# I2S_Audio.net
KiCad netlist of a schematic drawn in Altium Designer
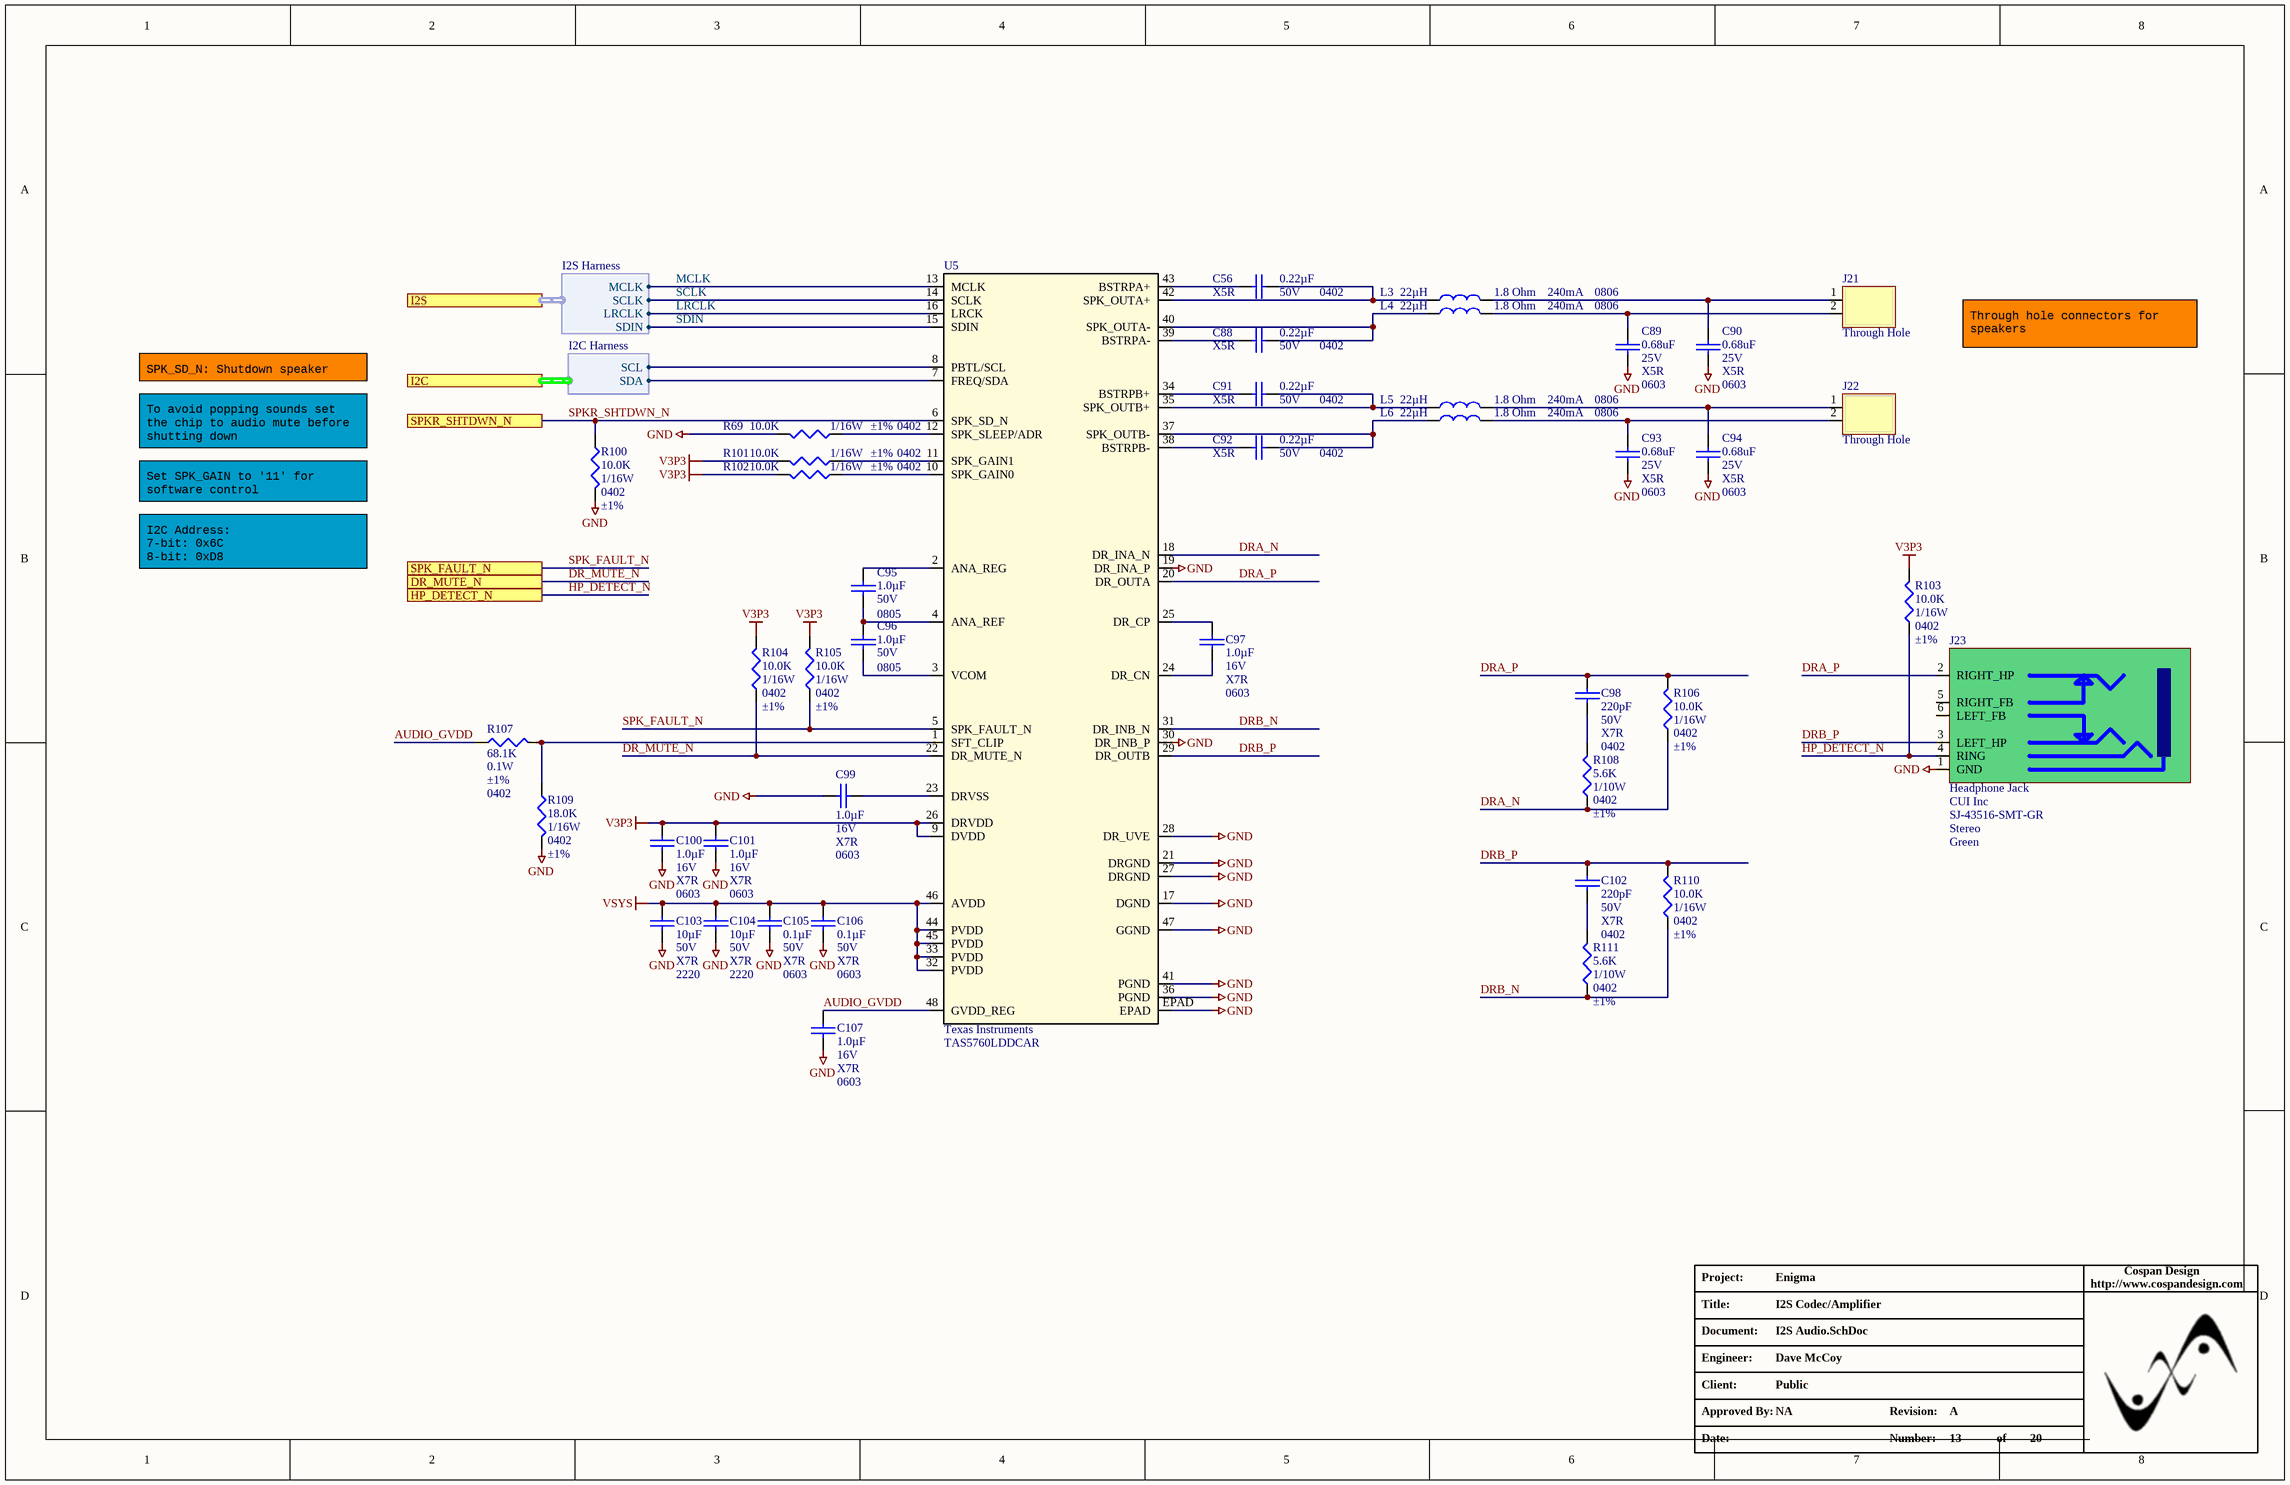
[diagram p0: I2S Audio.SchDoc]

(export (version "E")
  (design (tool "Eeschema 10.0.6"))
  (components
    (comp (ref "C56")
      (value "C_0402_0.22UF_50V")
      (footprint "C_0402")
      (description "CAP CER 0.22UF 50V X5R 0402")
      (fields
        (field (name "MANUFACTURER") "Taiyo Yuden")
        (field (name "MANUFACTURER PART NUMBER") "UMK105BJ224KV-F")
        (field (name "CAPACITANCE") "0.22µF")
        (field (name "VOLTAGE - RATED") "50V")
        (field (name "TEMPERATURE COEFFICIENT") "X5R")
        (field (name "PACKAGE / CASE") "0402")
      )
      (libsource (lib "Main Library") (part "C_0402_0.22UF_50V"))
    )
    (comp (ref "C88")
      (value "C_0402_0.22UF_50V")
      (footprint "C_0402")
      (description "CAP CER 0.22UF 50V X5R 0402")
      (fields
        (field (name "MANUFACTURER") "Taiyo Yuden")
        (field (name "MANUFACTURER PART NUMBER") "UMK105BJ224KV-F")
        (field (name "CAPACITANCE") "0.22µF")
        (field (name "VOLTAGE - RATED") "50V")
        (field (name "TEMPERATURE COEFFICIENT") "X5R")
        (field (name "PACKAGE / CASE") "0402")
      )
      (libsource (lib "Main Library") (part "C_0402_0.22UF_50V"))
    )
    (comp (ref "C89")
      (value "C_0603_0.68uF_25V")
      (footprint "C_ERA-0603")
      (description "CAP CER 0.68UF 25V X5R 0603")
      (fields
        (field (name "MANUFACTURER") "Wurth Electronics Inc.")
        (field (name "MANUFACTURER PART NUMBER") "885012106021")
        (field (name "CAPACITANCE") "0.68uF")
        (field (name "VOLTAGE - RATED") "25V")
        (field (name "TEMPERATURE COEFFICIENT") "X5R")
        (field (name "PACKAGE / CASE") "0603")
      )
      (libsource (lib "Cospan Design") (part "C_0603_0.68uF_25V"))
    )
    (comp (ref "C90")
      (value "C_0603_0.68uF_25V")
      (footprint "C_ERA-0603")
      (description "CAP CER 0.68UF 25V X5R 0603")
      (fields
        (field (name "MANUFACTURER") "Wurth Electronics Inc.")
        (field (name "MANUFACTURER PART NUMBER") "885012106021")
        (field (name "CAPACITANCE") "0.68uF")
        (field (name "VOLTAGE - RATED") "25V")
        (field (name "TEMPERATURE COEFFICIENT") "X5R")
        (field (name "PACKAGE / CASE") "0603")
      )
      (libsource (lib "Cospan Design") (part "C_0603_0.68uF_25V"))
    )
    (comp (ref "C91")
      (value "C_0402_0.22UF_50V")
      (footprint "C_0402")
      (description "CAP CER 0.22UF 50V X5R 0402")
      (fields
        (field (name "MANUFACTURER") "Taiyo Yuden")
        (field (name "MANUFACTURER PART NUMBER") "UMK105BJ224KV-F")
        (field (name "CAPACITANCE") "0.22µF")
        (field (name "VOLTAGE - RATED") "50V")
        (field (name "TEMPERATURE COEFFICIENT") "X5R")
        (field (name "PACKAGE / CASE") "0402")
      )
      (libsource (lib "Main Library") (part "C_0402_0.22UF_50V"))
    )
    (comp (ref "C92")
      (value "C_0402_0.22UF_50V")
      (footprint "C_0402")
      (description "CAP CER 0.22UF 50V X5R 0402")
      (fields
        (field (name "MANUFACTURER") "Taiyo Yuden")
        (field (name "MANUFACTURER PART NUMBER") "UMK105BJ224KV-F")
        (field (name "CAPACITANCE") "0.22µF")
        (field (name "VOLTAGE - RATED") "50V")
        (field (name "TEMPERATURE COEFFICIENT") "X5R")
        (field (name "PACKAGE / CASE") "0402")
      )
      (libsource (lib "Main Library") (part "C_0402_0.22UF_50V"))
    )
    (comp (ref "C93")
      (value "C_0603_0.68uF_25V")
      (footprint "C_ERA-0603")
      (description "CAP CER 0.68UF 25V X5R 0603")
      (fields
        (field (name "MANUFACTURER") "Wurth Electronics Inc.")
        (field (name "MANUFACTURER PART NUMBER") "885012106021")
        (field (name "CAPACITANCE") "0.68uF")
        (field (name "VOLTAGE - RATED") "25V")
        (field (name "TEMPERATURE COEFFICIENT") "X5R")
        (field (name "PACKAGE / CASE") "0603")
      )
      (libsource (lib "Cospan Design") (part "C_0603_0.68uF_25V"))
    )
    (comp (ref "C94")
      (value "C_0603_0.68uF_25V")
      (footprint "C_ERA-0603")
      (description "CAP CER 0.68UF 25V X5R 0603")
      (fields
        (field (name "MANUFACTURER") "Wurth Electronics Inc.")
        (field (name "MANUFACTURER PART NUMBER") "885012106021")
        (field (name "CAPACITANCE") "0.68uF")
        (field (name "VOLTAGE - RATED") "25V")
        (field (name "TEMPERATURE COEFFICIENT") "X5R")
        (field (name "PACKAGE / CASE") "0603")
      )
      (libsource (lib "Cospan Design") (part "C_0603_0.68uF_25V"))
    )
    (comp (ref "C95")
      (value "1.0uF")
      (footprint "C_ERA-0805")
      (description "CAP CER 1UF 50V X7R 0805")
      (fields
        (field (name "MANUFACTURER") "Murata Electronics North America")
        (field (name "MANUFACTURER PART NUMBER") "GRM21BR71H105KA12L")
        (field (name "CAPACITANCE") "1.0µF")
        (field (name "VOLTAGE - RATED") "50V")
        (field (name "PACKAGE / CASE") "0805")
      )
      (libsource (lib "Main Library") (part "C_0805_1.0uF_50V"))
    )
    (comp (ref "C96")
      (value "1.0uF")
      (footprint "C_ERA-0805")
      (description "CAP CER 1UF 50V X7R 0805")
      (fields
        (field (name "MANUFACTURER") "Murata Electronics North America")
        (field (name "MANUFACTURER PART NUMBER") "GRM21BR71H105KA12L")
        (field (name "CAPACITANCE") "1.0µF")
        (field (name "VOLTAGE - RATED") "50V")
        (field (name "PACKAGE / CASE") "0805")
      )
      (libsource (lib "Main Library") (part "C_0805_1.0uF_50V"))
    )
    (comp (ref "C97")
      (value "1.0uF")
      (footprint "C_ERA-0603")
      (description "CAP CER 1UF 16V 10% X7R 0603")
      (fields
        (field (name "MANUFACTURER") "Yageo")
        (field (name "MANUFACTURER PART NUMBER") "CC0603KRX7R7BB105")
        (field (name "CAPACITANCE") "1.0µF")
        (field (name "VOLTAGE - RATED") "16V")
        (field (name "TEMPERATURE COEFFICIENT") "X7R")
        (field (name "PACKAGE / CASE") "0603")
      )
      (libsource (lib "Main LibraryX") (part "C_0603_1.0uF_16V"))
    )
    (comp (ref "C98")
      (value "220pF")
      (footprint "C_0402")
      (description "CAP CER 220PF 50V 10% X7R 0402")
      (fields
        (field (name "MANUFACTURER") "Murata Electronics North America")
        (field (name "MANUFACTURER PART NUMBER") "GRM155R71H221KA01D")
        (field (name "CAPACITANCE") "220pF")
        (field (name "VOLTAGE - RATED") "50V")
        (field (name "TEMPERATURE COEFFICIENT") "X7R")
        (field (name "PACKAGE / CASE") "0402")
      )
      (libsource (lib "Main Library") (part "C_0402_220PF_50V"))
    )
    (comp (ref "C99")
      (value "1.0uF")
      (footprint "C_ERA-0603")
      (description "CAP CER 1UF 16V 10% X7R 0603")
      (fields
        (field (name "MANUFACTURER") "Yageo")
        (field (name "MANUFACTURER PART NUMBER") "CC0603KRX7R7BB105")
        (field (name "CAPACITANCE") "1.0µF")
        (field (name "VOLTAGE - RATED") "16V")
        (field (name "TEMPERATURE COEFFICIENT") "X7R")
        (field (name "PACKAGE / CASE") "0603")
      )
      (libsource (lib "Main LibraryX") (part "C_0603_1.0uF_16V"))
    )
    (comp (ref "C100")
      (value "1.0uF")
      (footprint "C_ERA-0603")
      (description "CAP CER 1UF 16V 10% X7R 0603")
      (fields
        (field (name "MANUFACTURER") "Yageo")
        (field (name "MANUFACTURER PART NUMBER") "CC0603KRX7R7BB105")
        (field (name "CAPACITANCE") "1.0µF")
        (field (name "VOLTAGE - RATED") "16V")
        (field (name "TEMPERATURE COEFFICIENT") "X7R")
        (field (name "PACKAGE / CASE") "0603")
      )
      (libsource (lib "Main LibraryX") (part "C_0603_1.0uF_16V"))
    )
    (comp (ref "C101")
      (value "1.0uF")
      (footprint "C_ERA-0603")
      (description "CAP CER 1UF 16V 10% X7R 0603")
      (fields
        (field (name "MANUFACTURER") "Yageo")
        (field (name "MANUFACTURER PART NUMBER") "CC0603KRX7R7BB105")
        (field (name "CAPACITANCE") "1.0µF")
        (field (name "VOLTAGE - RATED") "16V")
        (field (name "TEMPERATURE COEFFICIENT") "X7R")
        (field (name "PACKAGE / CASE") "0603")
      )
      (libsource (lib "Main LibraryX") (part "C_0603_1.0uF_16V"))
    )
    (comp (ref "C102")
      (value "220pF")
      (footprint "C_0402")
      (description "CAP CER 220PF 50V 10% X7R 0402")
      (fields
        (field (name "MANUFACTURER") "Murata Electronics North America")
        (field (name "MANUFACTURER PART NUMBER") "GRM155R71H221KA01D")
        (field (name "CAPACITANCE") "220pF")
        (field (name "VOLTAGE - RATED") "50V")
        (field (name "TEMPERATURE COEFFICIENT") "X7R")
        (field (name "PACKAGE / CASE") "0402")
      )
      (libsource (lib "Main Library") (part "C_0402_220PF_50V"))
    )
    (comp (ref "C103")
      (value "10µF")
      (footprint "C_ERA-2220")
      (description "CAP CER 10UF 50V X7R 20% 2220")
      (fields
        (field (name "MANUFACTURER") "TDK Corporation")
        (field (name "MANUFACTURER PART NUMBER") "C5750X7R1H106K230KB")
        (field (name "CAPACITANCE") "10µF")
        (field (name "VOLTAGE - RATED") "50V")
        (field (name "TEMPERATURE COEFFICIENT") "X7R")
        (field (name "PACKAGE / CASE") "2220")
      )
      (libsource (lib "Main LibraryX") (part "C_2220_10UF_50V"))
    )
    (comp (ref "C104")
      (value "10µF")
      (footprint "C_ERA-2220")
      (description "CAP CER 10UF 50V X7R 20% 2220")
      (fields
        (field (name "MANUFACTURER") "TDK Corporation")
        (field (name "MANUFACTURER PART NUMBER") "C5750X7R1H106K230KB")
        (field (name "CAPACITANCE") "10µF")
        (field (name "VOLTAGE - RATED") "50V")
        (field (name "TEMPERATURE COEFFICIENT") "X7R")
        (field (name "PACKAGE / CASE") "2220")
      )
      (libsource (lib "Main LibraryX") (part "C_2220_10UF_50V"))
    )
    (comp (ref "C105")
      (value "C_0603_0.1µF")
      (footprint "C_ERA-0603")
      (description "CAP CER 0.1UF 50V X7R 0603")
      (fields
        (field (name "MANUFACTURER") "Samsung Electro-Mechanics America, Inc.")
        (field (name "MANUFACTURER PART NUMBER") "CL10B104KB8SFNC")
        (field (name "CAPACITANCE") "0.1µF")
        (field (name "VOLTAGE - RATED") "50V")
        (field (name "TEMPERATURE COEFFICIENT") "X7R")
        (field (name "PACKAGE / CASE") "0603")
      )
      (libsource (lib "Cospan Design") (part "C_0603_0.1µF"))
    )
    (comp (ref "C106")
      (value "C_0603_0.1µF")
      (footprint "C_ERA-0603")
      (description "CAP CER 0.1UF 50V X7R 0603")
      (fields
        (field (name "MANUFACTURER") "Samsung Electro-Mechanics America, Inc.")
        (field (name "MANUFACTURER PART NUMBER") "CL10B104KB8SFNC")
        (field (name "CAPACITANCE") "0.1µF")
        (field (name "VOLTAGE - RATED") "50V")
        (field (name "TEMPERATURE COEFFICIENT") "X7R")
        (field (name "PACKAGE / CASE") "0603")
      )
      (libsource (lib "Cospan Design") (part "C_0603_0.1µF"))
    )
    (comp (ref "C107")
      (value "1.0uF")
      (footprint "C_ERA-0603")
      (description "CAP CER 1UF 16V 10% X7R 0603")
      (fields
        (field (name "MANUFACTURER") "Yageo")
        (field (name "MANUFACTURER PART NUMBER") "CC0603KRX7R7BB105")
        (field (name "CAPACITANCE") "1.0µF")
        (field (name "VOLTAGE - RATED") "16V")
        (field (name "TEMPERATURE COEFFICIENT") "X7R")
        (field (name "PACKAGE / CASE") "0603")
      )
      (libsource (lib "Main LibraryX") (part "C_0603_1.0uF_16V"))
    )
    (comp (ref "J21")
      (value "J_HDR1X2_JUMPER")
      (footprint "HDR_1X2")
      (description "CONN HEADER .100\" 2POS TIN PCB")
      (fields
        (field (name "MANUFACTURER") "Samtec")
        (field (name "MANUFACTURER PART NUMBER") "TSW-102-07-T-S")
        (field (name "MOUNTING TYPE") "Through Hole")
      )
      (libsource (lib "Main Library") (part "J_HDR1X2_JUMPER"))
    )
    (comp (ref "J22")
      (value "J_HDR1X2_JUMPER")
      (footprint "HDR_1X2")
      (description "CONN HEADER .100\" 2POS TIN PCB")
      (fields
        (field (name "MANUFACTURER") "Samtec")
        (field (name "MANUFACTURER PART NUMBER") "TSW-102-07-T-S")
        (field (name "MOUNTING TYPE") "Through Hole")
      )
      (libsource (lib "Main Library") (part "J_HDR1X2_JUMPER"))
    )
    (comp (ref "J23")
      (value "Headphone Jack")
      (footprint "HEADPHONE_JACK")
      (description "CONN AUDIO JACK 3.5MM 4COND SMD")
      (fields
        (field (name "MANUFACTURER") "CUI Inc")
        (field (name "MANUFACTURER PART NUMBER") "SJ-43516-SMT-GR")
        (field (name "SIGNAL LINES") "Stereo")
        (field (name "COLOR") "Green")
      )
      (libsource (lib "Main Library") (part "J_HEADPHONE_JACK"))
    )
    (comp (ref "L3")
      (value "CBC2016T220K")
      (footprint "L_0806")
      (description "INDUCTOR 22UH 10% 0806 SMD")
      (fields
        (field (name "MANUFACTURER") "Taiyo Yuden")
        (field (name "TOLERANCE") "±10%")
        (field (name "CURRENT") "240mA")
        (field (name "PACKAGE / CASE") "0806")
        (field (name "INDUCTANCE") "22µH")
        (field (name "DC RESISTANCE (DCR)") "1.8 Ohm")
      )
      (libsource (lib "Main Library") (part "L_0806_22uH"))
    )
    (comp (ref "L4")
      (value "CBC2016T220K")
      (footprint "L_0806")
      (description "INDUCTOR 22UH 10% 0806 SMD")
      (fields
        (field (name "MANUFACTURER") "Taiyo Yuden")
        (field (name "TOLERANCE") "±10%")
        (field (name "CURRENT") "240mA")
        (field (name "PACKAGE / CASE") "0806")
        (field (name "INDUCTANCE") "22µH")
        (field (name "DC RESISTANCE (DCR)") "1.8 Ohm")
      )
      (libsource (lib "Main Library") (part "L_0806_22uH"))
    )
    (comp (ref "L5")
      (value "CBC2016T220K")
      (footprint "L_0806")
      (description "INDUCTOR 22UH 10% 0806 SMD")
      (fields
        (field (name "MANUFACTURER") "Taiyo Yuden")
        (field (name "TOLERANCE") "±10%")
        (field (name "CURRENT") "240mA")
        (field (name "PACKAGE / CASE") "0806")
        (field (name "INDUCTANCE") "22µH")
        (field (name "DC RESISTANCE (DCR)") "1.8 Ohm")
      )
      (libsource (lib "Main Library") (part "L_0806_22uH"))
    )
    (comp (ref "L6")
      (value "CBC2016T220K")
      (footprint "L_0806")
      (description "INDUCTOR 22UH 10% 0806 SMD")
      (fields
        (field (name "MANUFACTURER") "Taiyo Yuden")
        (field (name "TOLERANCE") "±10%")
        (field (name "CURRENT") "240mA")
        (field (name "PACKAGE / CASE") "0806")
        (field (name "INDUCTANCE") "22µH")
        (field (name "DC RESISTANCE (DCR)") "1.8 Ohm")
      )
      (libsource (lib "Main Library") (part "L_0806_22uH"))
    )
    (comp (ref "R69")
      (value "R_0402_10.0K")
      (footprint "R_0402")
      (description "RES 10.0K OHM 1/16W 1% 0402 SMD")
      (fields
        (field (name "MANUFACTURER") "Stackpole Electronics Inc")
        (field (name "MANUFACTURER PART NUMBER") "RMCF0402FT10K0")
        (field (name "RESISTANCE IN OHMS") "10.0K")
        (field (name "POWER (WATTS)") "1/16W")
        (field (name "CASE") "0402")
        (field (name "TOLERANCE") "±1%")
      )
      (libsource (lib "Main Library") (part "R_0402_10.0K"))
    )
    (comp (ref "R100")
      (value "R_0402_10.0K")
      (footprint "R_0402")
      (description "RES 10.0K OHM 1/16W 1% 0402 SMD")
      (fields
        (field (name "MANUFACTURER") "Stackpole Electronics Inc")
        (field (name "MANUFACTURER PART NUMBER") "RMCF0402FT10K0")
        (field (name "RESISTANCE IN OHMS") "10.0K")
        (field (name "POWER (WATTS)") "1/16W")
        (field (name "CASE") "0402")
        (field (name "TOLERANCE") "±1%")
      )
      (libsource (lib "Main Library") (part "R_0402_10.0K"))
    )
    (comp (ref "R101")
      (value "R_0402_10.0K")
      (footprint "R_0402")
      (description "RES 10.0K OHM 1/16W 1% 0402 SMD")
      (fields
        (field (name "MANUFACTURER") "Stackpole Electronics Inc")
        (field (name "MANUFACTURER PART NUMBER") "RMCF0402FT10K0")
        (field (name "RESISTANCE IN OHMS") "10.0K")
        (field (name "POWER (WATTS)") "1/16W")
        (field (name "CASE") "0402")
        (field (name "TOLERANCE") "±1%")
      )
      (libsource (lib "Main Library") (part "R_0402_10.0K"))
    )
    (comp (ref "R102")
      (value "R_0402_10.0K")
      (footprint "R_0402")
      (description "RES 10.0K OHM 1/16W 1% 0402 SMD")
      (fields
        (field (name "MANUFACTURER") "Stackpole Electronics Inc")
        (field (name "MANUFACTURER PART NUMBER") "RMCF0402FT10K0")
        (field (name "RESISTANCE IN OHMS") "10.0K")
        (field (name "POWER (WATTS)") "1/16W")
        (field (name "CASE") "0402")
        (field (name "TOLERANCE") "±1%")
      )
      (libsource (lib "Main Library") (part "R_0402_10.0K"))
    )
    (comp (ref "R103")
      (value "R_0402_10.0K")
      (footprint "R_0402")
      (description "RES 10.0K OHM 1/16W 1% 0402 SMD")
      (fields
        (field (name "MANUFACTURER") "Stackpole Electronics Inc")
        (field (name "MANUFACTURER PART NUMBER") "RMCF0402FT10K0")
        (field (name "RESISTANCE IN OHMS") "10.0K")
        (field (name "POWER (WATTS)") "1/16W")
        (field (name "CASE") "0402")
        (field (name "TOLERANCE") "±1%")
      )
      (libsource (lib "Main Library") (part "R_0402_10.0K"))
    )
    (comp (ref "R104")
      (value "R_0402_10.0K")
      (footprint "R_0402")
      (description "RES 10.0K OHM 1/16W 1% 0402 SMD")
      (fields
        (field (name "MANUFACTURER") "Stackpole Electronics Inc")
        (field (name "MANUFACTURER PART NUMBER") "RMCF0402FT10K0")
        (field (name "RESISTANCE IN OHMS") "10.0K")
        (field (name "POWER (WATTS)") "1/16W")
        (field (name "CASE") "0402")
        (field (name "TOLERANCE") "±1%")
      )
      (libsource (lib "Main Library") (part "R_0402_10.0K"))
    )
    (comp (ref "R105")
      (value "R_0402_10.0K")
      (footprint "R_0402")
      (description "RES 10.0K OHM 1/16W 1% 0402 SMD")
      (fields
        (field (name "MANUFACTURER") "Stackpole Electronics Inc")
        (field (name "MANUFACTURER PART NUMBER") "RMCF0402FT10K0")
        (field (name "RESISTANCE IN OHMS") "10.0K")
        (field (name "POWER (WATTS)") "1/16W")
        (field (name "CASE") "0402")
        (field (name "TOLERANCE") "±1%")
      )
      (libsource (lib "Main Library") (part "R_0402_10.0K"))
    )
    (comp (ref "R106")
      (value "R_0402_10.0K")
      (footprint "R_0402")
      (description "RES 10.0K OHM 1/16W 1% 0402 SMD")
      (fields
        (field (name "MANUFACTURER") "Stackpole Electronics Inc")
        (field (name "MANUFACTURER PART NUMBER") "RMCF0402FT10K0")
        (field (name "RESISTANCE IN OHMS") "10.0K")
        (field (name "POWER (WATTS)") "1/16W")
        (field (name "CASE") "0402")
        (field (name "TOLERANCE") "±1%")
      )
      (libsource (lib "Main Library") (part "R_0402_10.0K"))
    )
    (comp (ref "R107")
      (value "R_0402_68.1K")
      (footprint "R_0402")
      (description "RES 68.1K OHM 1/10W 1% 0402 SMD")
      (fields
        (field (name "MANUFACTURER") "Panasonic - ECG")
        (field (name "MANUFACTURER PART NUMBER") "ERJ-2RKF6812X")
        (field (name "RESISTANCE IN OHMS") "68.1K")
        (field (name "POWER (WATTS)") "0.1W")
        (field (name "TOLERANCE") "±1%")
        (field (name "CASE") "0402")
      )
      (libsource (lib "Main Library") (part "R_0402_68.1K"))
    )
    (comp (ref "R108")
      (value "5.6k Ohms")
      (footprint "R_0402")
      (description "RES 5.60K OHM 1/10W 1% 0402 SMD")
      (fields
        (field (name "MANUFACTURER") "Yageo")
        (field (name "MANUFACTURER PART NUMBER") "RC0402FR-075K6L")
        (field (name "RESISTANCE IN OHMS") "5.6K")
        (field (name "POWER (WATTS)") "1/10W")
        (field (name "CASE") "0402")
        (field (name "TOLERANCE") "±1%")
      )
      (libsource (lib "Main LibraryX") (part "R_0402_5.6K"))
    )
    (comp (ref "R109")
      (value "18.0k Ohms")
      (footprint "R_0402")
      (description "RES SMD 18K OHM 1% 1/16W 0402")
      (fields
        (field (name "MANUFACTURER") "Yageo")
        (field (name "MANUFACTURER PART NUMBER") "RC0402FR-0718KL")
        (field (name "RESISTANCE IN OHMS") "18.0K")
        (field (name "POWER (WATTS)") "1/16W")
        (field (name "CASE") "0402")
        (field (name "TOLERANCE") "±1%")
      )
      (libsource (lib "Cospan Design") (part "R_0402_18.0K"))
    )
    (comp (ref "R110")
      (value "R_0402_10.0K")
      (footprint "R_0402")
      (description "RES 10.0K OHM 1/16W 1% 0402 SMD")
      (fields
        (field (name "MANUFACTURER") "Stackpole Electronics Inc")
        (field (name "MANUFACTURER PART NUMBER") "RMCF0402FT10K0")
        (field (name "RESISTANCE IN OHMS") "10.0K")
        (field (name "POWER (WATTS)") "1/16W")
        (field (name "CASE") "0402")
        (field (name "TOLERANCE") "±1%")
      )
      (libsource (lib "Main Library") (part "R_0402_10.0K"))
    )
    (comp (ref "R111")
      (value "5.6k Ohms")
      (footprint "R_0402")
      (description "RES 5.60K OHM 1/10W 1% 0402 SMD")
      (fields
        (field (name "MANUFACTURER") "Yageo")
        (field (name "MANUFACTURER PART NUMBER") "RC0402FR-075K6L")
        (field (name "RESISTANCE IN OHMS") "5.6K")
        (field (name "POWER (WATTS)") "1/10W")
        (field (name "CASE") "0402")
        (field (name "TOLERANCE") "±1%")
      )
      (libsource (lib "Main LibraryX") (part "R_0402_5.6K"))
    )
    (comp (ref "U5")
      (value "U_TAS5760LDDCAR")
      (footprint "DCA48_6P4X3P6")
      (description "IC AUDIO AMP DGTL D 48HTSSOP")
      (fields
        (field (name "MANUFACTURER 1") "Texas Instruments")
        (field (name "MANUFACTURER PART NUMBER 1") "TAS5760LDDCAR")
      )
      (libsource (lib "Cospan Design") (part "U_TAS5760LDDCAR"))
    )
  )
  (nets
    (net (code "4") (name "/AUDIO_GVDD") (class "Default")
      (node (ref "C107") (pin "2") (pinfunction "2_2") (pintype "passive"))
      (node (ref "R107") (pin "1") (pinfunction "1_1") (pintype "passive"))
      (node (ref "U5") (pin "48") (pinfunction "GVDD_REG_48") (pintype "passive"))
    )
    (net (code "5") (name "/DRA_N") (class "Default")
      (node (ref "R106") (pin "2") (pinfunction "2_2") (pintype "passive"))
      (node (ref "R108") (pin "2") (pinfunction "2_2") (pintype "passive"))
      (node (ref "U5") (pin "18") (pinfunction "DR_INA_N_18") (pintype "passive"))
    )
    (net (code "6") (name "/DRA_P") (class "Default")
      (node (ref "C98") (pin "2") (pinfunction "2_2") (pintype "passive"))
      (node (ref "J23") (pin "2") (pinfunction "RIGHT_HP_2") (pintype "passive"))
      (node (ref "R106") (pin "1") (pinfunction "1_1") (pintype "passive"))
      (node (ref "U5") (pin "20") (pinfunction "DR_OUTA_20") (pintype "passive"))
    )
    (net (code "7") (name "/DRB_N") (class "Default")
      (node (ref "R110") (pin "2") (pinfunction "2_2") (pintype "passive"))
      (node (ref "R111") (pin "2") (pinfunction "2_2") (pintype "passive"))
      (node (ref "U5") (pin "31") (pinfunction "DR_INB_N_31") (pintype "passive"))
    )
    (net (code "8") (name "/DRB_P") (class "Default")
      (node (ref "C102") (pin "2") (pinfunction "2_2") (pintype "passive"))
      (node (ref "J23") (pin "3") (pinfunction "LEFT_HP_3") (pintype "passive"))
      (node (ref "R110") (pin "1") (pinfunction "1_1") (pintype "passive"))
      (node (ref "U5") (pin "29") (pinfunction "DR_OUTB_29") (pintype "passive"))
    )
    (net (code "9") (name "/DR_MUTE_N") (class "Default")
      (node (ref "R104") (pin "1") (pinfunction "1_1") (pintype "passive"))
      (node (ref "U5") (pin "22") (pinfunction "DR_MUTE_N_22") (pintype "passive"))
    )
    (net (code "10") (name "/HP_DETECT_N") (class "Default")
      (node (ref "J23") (pin "4") (pinfunction "RING_4") (pintype "passive"))
      (node (ref "R103") (pin "2") (pinfunction "2_2") (pintype "passive"))
    )
    (net (code "11") (name "/LRCLK") (class "Default")
      (node (ref "U5") (pin "16") (pinfunction "LRCK_16") (pintype "passive"))
    )
    (net (code "12") (name "/MCLK") (class "Default")
      (node (ref "U5") (pin "13") (pinfunction "MCLK_13") (pintype "passive"))
    )
    (net (code "13") (name "/SCL") (class "Default")
      (node (ref "U5") (pin "8") (pinfunction "PBTL/SCL_8") (pintype "passive"))
    )
    (net (code "14") (name "/SCLK") (class "Default")
      (node (ref "U5") (pin "14") (pinfunction "SCLK_14") (pintype "passive"))
    )
    (net (code "15") (name "/SDA") (class "Default")
      (node (ref "U5") (pin "7") (pinfunction "FREQ/SDA_7") (pintype "passive"))
    )
    (net (code "16") (name "/SDIN") (class "Default")
      (node (ref "U5") (pin "15") (pinfunction "SDIN_15") (pintype "passive"))
    )
    (net (code "17") (name "/SPKR_SHTDWN_N") (class "Default")
      (node (ref "R100") (pin "2") (pinfunction "2_2") (pintype "passive"))
      (node (ref "U5") (pin "6") (pinfunction "SPK_SD_N_6") (pintype "passive"))
    )
    (net (code "18") (name "/SPK_FAULT_N") (class "Default")
      (node (ref "R105") (pin "1") (pinfunction "1_1") (pintype "passive"))
      (node (ref "U5") (pin "5") (pinfunction "SPK_FAULT_N_5") (pintype "passive"))
    )
    (net (code "21") (name "GND") (class "Default")
      (node (ref "C100") (pin "1") (pinfunction "1_1") (pintype "passive"))
      (node (ref "C101") (pin "1") (pinfunction "1_1") (pintype "passive"))
      (node (ref "C103") (pin "1") (pinfunction "1_1") (pintype "passive"))
      (node (ref "C104") (pin "1") (pinfunction "1_1") (pintype "passive"))
      (node (ref "C105") (pin "1") (pinfunction "1_1") (pintype "passive"))
      (node (ref "C106") (pin "1") (pinfunction "1_1") (pintype "passive"))
      (node (ref "C107") (pin "1") (pinfunction "1_1") (pintype "passive"))
      (node (ref "C89") (pin "1") (pinfunction "1_1") (pintype "passive"))
      (node (ref "C90") (pin "1") (pinfunction "1_1") (pintype "passive"))
      (node (ref "C93") (pin "1") (pinfunction "1_1") (pintype "passive"))
      (node (ref "C94") (pin "1") (pinfunction "1_1") (pintype "passive"))
      (node (ref "C99") (pin "1") (pinfunction "1_1") (pintype "passive"))
      (node (ref "J23") (pin "1") (pinfunction "GND_1") (pintype "passive"))
      (node (ref "R100") (pin "1") (pinfunction "1_1") (pintype "passive"))
      (node (ref "R109") (pin "2") (pinfunction "2_2") (pintype "passive"))
      (node (ref "R69") (pin "1") (pinfunction "1_1") (pintype "passive"))
      (node (ref "U5") (pin "17") (pinfunction "DGND_17") (pintype "passive"))
      (node (ref "U5") (pin "19") (pinfunction "DR_INA_P_19") (pintype "passive"))
      (node (ref "U5") (pin "21") (pinfunction "DRGND_21") (pintype "passive"))
      (node (ref "U5") (pin "27") (pinfunction "DRGND_27") (pintype "passive"))
      (node (ref "U5") (pin "28") (pinfunction "DR_UVE_28") (pintype "passive"))
      (node (ref "U5") (pin "30") (pinfunction "DR_INB_P_30") (pintype "passive"))
      (node (ref "U5") (pin "36") (pinfunction "PGND_36") (pintype "passive"))
      (node (ref "U5") (pin "41") (pinfunction "PGND_41") (pintype "passive"))
      (node (ref "U5") (pin "47") (pinfunction "GGND_47") (pintype "passive"))
      (node (ref "U5") (pin "EPAD") (pinfunction "EPAD_EPAD") (pintype "passive"))
    )
    (net (code "22") (name "Net-(C89-Pad2)") (class "Default")
      (node (ref "C89") (pin "2") (pinfunction "2_2") (pintype "passive"))
      (node (ref "J21") (pin "2") (pinfunction "2_2") (pintype "passive"))
      (node (ref "L4") (pin "2") (pintype "passive"))
    )
    (net (code "23") (name "Net-(C90-Pad2)") (class "Default")
      (node (ref "C90") (pin "2") (pinfunction "2_2") (pintype "passive"))
      (node (ref "J21") (pin "1") (pinfunction "1_1") (pintype "passive"))
      (node (ref "L3") (pin "2") (pintype "passive"))
    )
    (net (code "24") (name "Net-(C93-Pad2)") (class "Default")
      (node (ref "C93") (pin "2") (pinfunction "2_2") (pintype "passive"))
      (node (ref "J22") (pin "2") (pinfunction "2_2") (pintype "passive"))
      (node (ref "L6") (pin "2") (pintype "passive"))
    )
    (net (code "25") (name "Net-(C94-Pad2)") (class "Default")
      (node (ref "C94") (pin "2") (pinfunction "2_2") (pintype "passive"))
      (node (ref "J22") (pin "1") (pinfunction "1_1") (pintype "passive"))
      (node (ref "L5") (pin "2") (pintype "passive"))
    )
    (net (code "26") (name "Net-(C98-Pad1)") (class "Default")
      (node (ref "C98") (pin "1") (pinfunction "1_1") (pintype "passive"))
      (node (ref "R108") (pin "1") (pinfunction "1_1") (pintype "passive"))
    )
    (net (code "27") (name "Net-(C102-Pad1)") (class "Default")
      (node (ref "C102") (pin "1") (pinfunction "1_1") (pintype "passive"))
      (node (ref "R111") (pin "1") (pinfunction "1_1") (pintype "passive"))
    )
    (net (code "28") (name "Net-(U5-ANA_REF)") (class "Default")
      (node (ref "C95") (pin "1") (pinfunction "1_1") (pintype "passive"))
      (node (ref "C96") (pin "2") (pinfunction "2_2") (pintype "passive"))
      (node (ref "U5") (pin "4") (pinfunction "ANA_REF_4") (pintype "passive"))
    )
    (net (code "29") (name "Net-(U5-ANA_REG)") (class "Default")
      (node (ref "C95") (pin "2") (pinfunction "2_2") (pintype "passive"))
      (node (ref "U5") (pin "2") (pinfunction "ANA_REG_2") (pintype "passive"))
    )
    (net (code "30") (name "Net-(U5-BSTRPA+)") (class "Default")
      (node (ref "C56") (pin "2") (pinfunction "2_2") (pintype "passive"))
      (node (ref "U5") (pin "43") (pinfunction "BSTRPA+_43") (pintype "passive"))
    )
    (net (code "31") (name "Net-(U5-BSTRPA-)") (class "Default")
      (node (ref "C88") (pin "2") (pinfunction "2_2") (pintype "passive"))
      (node (ref "U5") (pin "39") (pinfunction "BSTRPA-_39") (pintype "passive"))
    )
    (net (code "32") (name "Net-(U5-BSTRPB+)") (class "Default")
      (node (ref "C91") (pin "2") (pinfunction "2_2") (pintype "passive"))
      (node (ref "U5") (pin "34") (pinfunction "BSTRPB+_34") (pintype "passive"))
    )
    (net (code "33") (name "Net-(U5-BSTRPB-)") (class "Default")
      (node (ref "C92") (pin "2") (pinfunction "2_2") (pintype "passive"))
      (node (ref "U5") (pin "38") (pinfunction "BSTRPB-_38") (pintype "passive"))
    )
    (net (code "34") (name "Net-(U5-DRVSS)") (class "Default")
      (node (ref "C99") (pin "2") (pinfunction "2_2") (pintype "passive"))
      (node (ref "U5") (pin "23") (pinfunction "DRVSS_23") (pintype "passive"))
    )
    (net (code "35") (name "Net-(U5-DR_CN)") (class "Default")
      (node (ref "C97") (pin "1") (pinfunction "1_1") (pintype "passive"))
      (node (ref "U5") (pin "24") (pinfunction "DR_CN_24") (pintype "passive"))
    )
    (net (code "36") (name "Net-(U5-DR_CP)") (class "Default")
      (node (ref "C97") (pin "2") (pinfunction "2_2") (pintype "passive"))
      (node (ref "U5") (pin "25") (pinfunction "DR_CP_25") (pintype "passive"))
    )
    (net (code "37") (name "Net-(U5-SFT_CLIP)") (class "Default")
      (node (ref "R107") (pin "2") (pinfunction "2_2") (pintype "passive"))
      (node (ref "R109") (pin "1") (pinfunction "1_1") (pintype "passive"))
      (node (ref "U5") (pin "1") (pinfunction "SFT_CLIP_1") (pintype "passive"))
    )
    (net (code "38") (name "Net-(U5-SPK_GAIN0)") (class "Default")
      (node (ref "R102") (pin "2") (pinfunction "2_2") (pintype "passive"))
      (node (ref "U5") (pin "10") (pinfunction "SPK_GAIN0_10") (pintype "passive"))
    )
    (net (code "39") (name "Net-(U5-SPK_GAIN1)") (class "Default")
      (node (ref "R101") (pin "2") (pinfunction "2_2") (pintype "passive"))
      (node (ref "U5") (pin "11") (pinfunction "SPK_GAIN1_11") (pintype "passive"))
    )
    (net (code "40") (name "Net-(U5-SPK_OUTA+)") (class "Default")
      (node (ref "C56") (pin "1") (pinfunction "1_1") (pintype "passive"))
      (node (ref "L3") (pin "1") (pintype "passive"))
      (node (ref "U5") (pin "42") (pinfunction "SPK_OUTA+_42") (pintype "passive"))
    )
    (net (code "41") (name "Net-(U5-SPK_OUTA-)") (class "Default")
      (node (ref "C88") (pin "1") (pinfunction "1_1") (pintype "passive"))
      (node (ref "L4") (pin "1") (pintype "passive"))
      (node (ref "U5") (pin "40") (pinfunction "SPK_OUTA-_40") (pintype "passive"))
    )
    (net (code "42") (name "Net-(U5-SPK_OUTB+)") (class "Default")
      (node (ref "C91") (pin "1") (pinfunction "1_1") (pintype "passive"))
      (node (ref "L5") (pin "1") (pintype "passive"))
      (node (ref "U5") (pin "35") (pinfunction "SPK_OUTB+_35") (pintype "passive"))
    )
    (net (code "43") (name "Net-(U5-SPK_OUTB-)") (class "Default")
      (node (ref "C92") (pin "1") (pinfunction "1_1") (pintype "passive"))
      (node (ref "L6") (pin "1") (pintype "passive"))
      (node (ref "U5") (pin "37") (pinfunction "SPK_OUTB-_37") (pintype "passive"))
    )
    (net (code "44") (name "Net-(U5-SPK_SLEEP{slash}ADR)") (class "Default")
      (node (ref "R69") (pin "2") (pinfunction "2_2") (pintype "passive"))
      (node (ref "U5") (pin "12") (pinfunction "SPK_SLEEP/ADR_12") (pintype "passive"))
    )
    (net (code "45") (name "Net-(U5-VCOM)") (class "Default")
      (node (ref "C96") (pin "1") (pinfunction "1_1") (pintype "passive"))
      (node (ref "U5") (pin "3") (pinfunction "VCOM_3") (pintype "passive"))
    )
    (net (code "46") (name "V3P3") (class "Default")
      (node (ref "C100") (pin "2") (pinfunction "2_2") (pintype "passive"))
      (node (ref "C101") (pin "2") (pinfunction "2_2") (pintype "passive"))
      (node (ref "R101") (pin "1") (pinfunction "1_1") (pintype "passive"))
      (node (ref "R102") (pin "1") (pinfunction "1_1") (pintype "passive"))
      (node (ref "R103") (pin "1") (pinfunction "1_1") (pintype "passive"))
      (node (ref "R104") (pin "2") (pinfunction "2_2") (pintype "passive"))
      (node (ref "R105") (pin "2") (pinfunction "2_2") (pintype "passive"))
      (node (ref "U5") (pin "26") (pinfunction "DRVDD_26") (pintype "passive"))
      (node (ref "U5") (pin "9") (pinfunction "DVDD_9") (pintype "passive"))
    )
    (net (code "47") (name "VSYS") (class "Default")
      (node (ref "C103") (pin "2") (pinfunction "2_2") (pintype "passive"))
      (node (ref "C104") (pin "2") (pinfunction "2_2") (pintype "passive"))
      (node (ref "C105") (pin "2") (pinfunction "2_2") (pintype "passive"))
      (node (ref "C106") (pin "2") (pinfunction "2_2") (pintype "passive"))
      (node (ref "U5") (pin "32") (pinfunction "PVDD_32") (pintype "passive"))
      (node (ref "U5") (pin "33") (pinfunction "PVDD_33") (pintype "passive"))
      (node (ref "U5") (pin "44") (pinfunction "PVDD_44") (pintype "passive"))
      (node (ref "U5") (pin "45") (pinfunction "PVDD_45") (pintype "passive"))
      (node (ref "U5") (pin "46") (pinfunction "AVDD_46") (pintype "passive"))
    )
    (net (code "48") (name "unconnected-(J23-LEFT_FB-Pad6)") (class "Default")
      (node (ref "J23") (pin "6") (pinfunction "LEFT_FB_6") (pintype "passive"))
    )
    (net (code "49") (name "unconnected-(J23-RIGHT_FB-Pad5)") (class "Default")
      (node (ref "J23") (pin "5") (pinfunction "RIGHT_FB_5") (pintype "passive"))
    )
  )
)
